# X.net
KiCad netlist of a schematic drawn in EAGLE
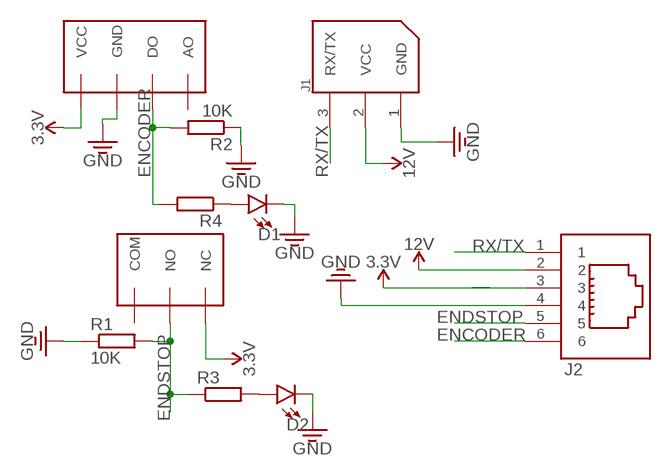
[diagram p0: schematic, sheet 1]

(export (version "E")
  (design (tool "Eeschema 10.0.6"))
  (components
    (comp (ref "D1")
      (value "LED5MM")
      (footprint "eagle-import:LED_5MM")
      (libsource (lib "eagle-import") (part "LED5MM"))
    )
    (comp (ref "D2")
      (value "LED5MM")
      (footprint "eagle-import:LED_5MM")
      (libsource (lib "eagle-import") (part "LED5MM"))
    )
    (comp (ref "J1")
      (value "22-03-5035")
      (footprint "eagle-import:5267-3")
      (libsource (lib "eagle-import") (part "22-03-5035"))
    )
    (comp (ref "J2")
      (value "615006138421")
      (footprint "eagle-import:615006138421")
      (libsource (lib "eagle-import") (part "615006138421"))
    )
    (comp (ref "R1")
      (value "10K")
      (footprint "eagle-import:0204_7")
      (libsource (lib "eagle-import") (part "R-EU_0204/7"))
    )
    (comp (ref "R2")
      (value "10K")
      (footprint "eagle-import:0204_7")
      (libsource (lib "eagle-import") (part "R-EU_0204/7"))
    )
    (comp (ref "R3")
      (value "R-EU_0204/7")
      (footprint "eagle-import:0204_7")
      (libsource (lib "eagle-import") (part "R-EU_0204/7"))
    )
    (comp (ref "R4")
      (value "R-EU_0204/7")
      (footprint "eagle-import:0204_7")
      (libsource (lib "eagle-import") (part "R-EU_0204/7"))
    )
    (comp (ref "U$1")
      (value "OPTICAL_ENCODER_FC-01")
      (footprint "eagle-import:OPTICAL_ENCODER_FC-01")
      (libsource (lib "eagle-import") (part "OPTICAL_ENCODER_FC-01"))
    )
    (comp (ref "U$2")
      (value "ENDSTOP")
      (footprint "eagle-import:ENDSTOP")
      (libsource (lib "eagle-import") (part "ENDSTOP"))
    )
  )
  (nets
    (net (code "1") (name "/ENCODER") (class "Default")
      (node (ref "J2") (pin "6") (pinfunction "6_6") (pintype "passive"))
      (node (ref "R2") (pin "2") (pinfunction "2_2") (pintype "passive"))
      (node (ref "R4") (pin "2") (pinfunction "2_2") (pintype "passive"))
      (node (ref "U$1") (pin "DO") (pinfunction "DO_DO") (pintype "bidirectional"))
    )
    (net (code "2") (name "/ENDSTOP") (class "Default")
      (node (ref "J2") (pin "5") (pinfunction "5_5") (pintype "passive"))
      (node (ref "R1") (pin "2") (pinfunction "2_2") (pintype "passive"))
      (node (ref "R3") (pin "1") (pinfunction "1_1") (pintype "passive"))
      (node (ref "U$2") (pin "NO") (pinfunction "NO_NO") (pintype "bidirectional"))
    )
    (net (code "3") (name "/RX{slash}TX") (class "Default")
      (node (ref "J1") (pin "3") (pinfunction "RX/TX_3") (pintype "bidirectional"))
      (node (ref "J2") (pin "1") (pinfunction "1_1") (pintype "passive"))
    )
    (net (code "4") (name "3.3V") (class "Default")
      (node (ref "J2") (pin "3") (pinfunction "3_3") (pintype "passive"))
      (node (ref "U$1") (pin "VCC") (pinfunction "VCC_VCC") (pintype "bidirectional"))
      (node (ref "U$2") (pin "NC") (pinfunction "NC_NC") (pintype "bidirectional"))
    )
    (net (code "5") (name "12V") (class "Default")
      (node (ref "J1") (pin "2") (pinfunction "VCC_2") (pintype "bidirectional"))
      (node (ref "J2") (pin "2") (pinfunction "2_2") (pintype "passive"))
    )
    (net (code "6") (name "GND") (class "Default")
      (node (ref "D1") (pin "K") (pinfunction "C_K") (pintype "passive"))
      (node (ref "D2") (pin "K") (pinfunction "C_K") (pintype "passive"))
      (node (ref "J1") (pin "1") (pinfunction "GND_1") (pintype "bidirectional"))
      (node (ref "J2") (pin "4") (pinfunction "4_4") (pintype "passive"))
      (node (ref "R1") (pin "1") (pinfunction "1_1") (pintype "passive"))
      (node (ref "R2") (pin "1") (pinfunction "1_1") (pintype "passive"))
      (node (ref "U$1") (pin "GND") (pinfunction "GND_GND") (pintype "bidirectional"))
    )
    (net (code "7") (name "Net-(D1-PadA)") (class "Default")
      (node (ref "D1") (pin "A") (pinfunction "A_A") (pintype "passive"))
      (node (ref "R4") (pin "1") (pinfunction "1_1") (pintype "passive"))
    )
    (net (code "8") (name "Net-(D2-PadA)") (class "Default")
      (node (ref "D2") (pin "A") (pinfunction "A_A") (pintype "passive"))
      (node (ref "R3") (pin "2") (pinfunction "2_2") (pintype "passive"))
    )
    (net (code "9") (name "unconnected-(U$1-PadAO)") (class "Default")
      (node (ref "U$1") (pin "AO") (pinfunction "AO_AO") (pintype "bidirectional"))
    )
    (net (code "10") (name "unconnected-(U$2-PadCOM)") (class "Default")
      (node (ref "U$2") (pin "COM") (pinfunction "COM_COM") (pintype "bidirectional"))
    )
  )
)
